# sheet_2_AnalogHeart.net
KiCad netlist of a schematic drawn in Altium Designer
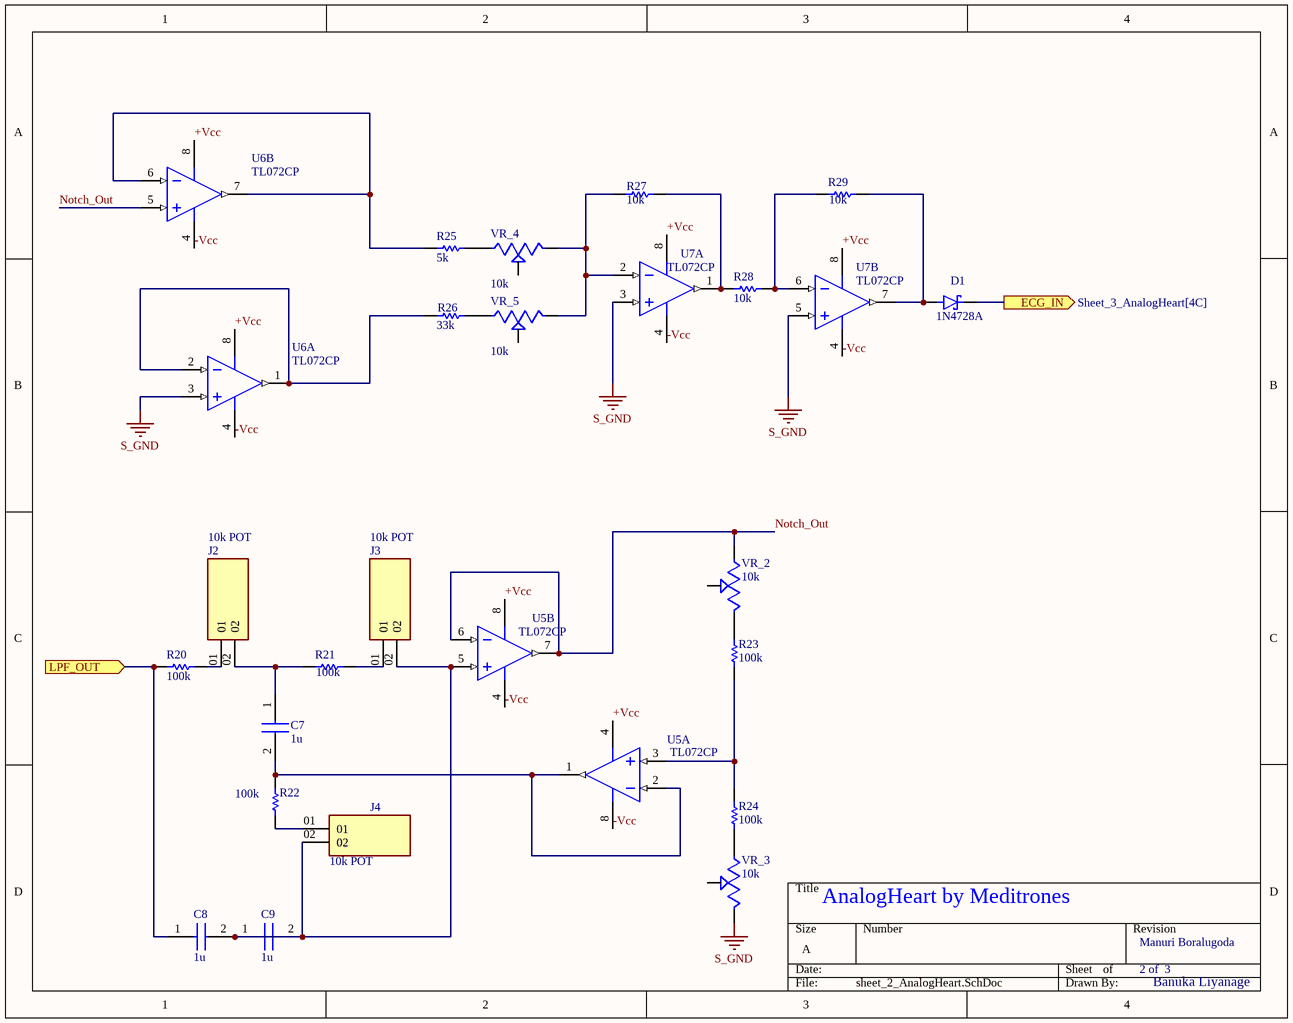
[diagram p0: sheet_2_AnalogHeart.SchDoc]

(export (version "E")
  (design (tool "Eeschema 10.0.6"))
  (components
    (comp (ref "C7")
      (value "1u")
      (footprint "SamacSys:CAPC2012X94N")
      (description "Capacitor")
      (fields
        (field (name "MANUFACTURER_PART_NUMBER") "08055A331FAT2A")
        (field (name "MOUSER PART NUMBER") "581-08055A331FAT2A")
      )
      (libsource (lib "*") (part "08055A331FAT2A"))
    )
    (comp (ref "C8")
      (value "1u")
      (footprint "SamacSys:CAPC2012X94N")
      (description "Capacitor")
      (fields
        (field (name "MANUFACTURER_PART_NUMBER") "08055A331FAT2A")
        (field (name "MOUSER PART NUMBER") "581-08055A331FAT2A")
      )
      (libsource (lib "*") (part "08055A331FAT2A"))
    )
    (comp (ref "C9")
      (value "1u")
      (footprint "SamacSys:CAPC2012X94N")
      (description "Capacitor")
      (fields
        (field (name "MANUFACTURER_PART_NUMBER") "08055A331FAT2A")
        (field (name "MOUSER PART NUMBER") "581-08055A331FAT2A")
      )
      (libsource (lib "*") (part "08055A331FAT2A"))
    )
    (comp (ref "D1")
      (value "1N4728A")
      (footprint "DIOAD1036W78L463D272")
      (description "Ð¡Ñ‚Ð°Ð±Ð¸Ð»Ð¸Ñ‚Ñ€Ð¾Ð½ 3,3 Ð’ 1 Ð’Ñ‚ Â± 5% ÑÐ¾ ÑÐºÐ²Ð¾Ð·Ð½Ñ‹Ð¼ Ð¾Ñ‚Ð²ÐµÑ€ÑÑ‚Ð¸ÐµÐ¼ DO-41")
      (fields (field (name "MF") "ON Semiconductor"))
      (libsource (lib "1N4728A") (part "1N4728A"))
    )
    (comp (ref "J2")
      (value "10k POT")
      (footprint "SAMTEC_MTSW-102-11-T-S-640")
      (fields (field (name "MP") "MTSW-102-11-T-S-640"))
      (libsource (lib "MTSW-102-11-T-S-640") (part "MTSW-102-11-T-S-640"))
    )
    (comp (ref "J3")
      (value "10k POT")
      (footprint "SAMTEC_MTSW-102-11-T-S-640")
      (fields (field (name "MP") "MTSW-102-11-T-S-640"))
      (libsource (lib "MTSW-102-11-T-S-640") (part "MTSW-102-11-T-S-640"))
    )
    (comp (ref "J4")
      (value "10k POT")
      (footprint "SAMTEC_MTSW-102-11-T-S-640")
      (fields (field (name "MP") "MTSW-102-11-T-S-640"))
      (libsource (lib "") (part "MTSW-102-11-T-S-640_1"))
    )
    (comp (ref "R20")
      (value "100k")
      (footprint "RESC2013X50X30NL20T20")
      (fields (field (name "MANUFACTURER") "Vishay Dale") (field (name "PART NUMBER") "CRCW080510R0FKEA"))
      (libsource (lib "Altium Content Vault") (part "RES"))
    )
    (comp (ref "R21")
      (value "100k")
      (footprint "RESC2013X50X30NL20T20")
      (fields (field (name "MANUFACTURER") "Vishay Dale") (field (name "PART NUMBER") "CRCW080510R0FKEA"))
      (libsource (lib "Altium Content Vault") (part "RES"))
    )
    (comp (ref "R22")
      (value "100k")
      (footprint "RESC2013X50X30NL20T20")
      (fields (field (name "MANUFACTURER") "Vishay Dale") (field (name "PART NUMBER") "CRCW080510R0FKEA"))
      (libsource (lib "Altium Content Vault") (part "RES"))
    )
    (comp (ref "R23")
      (value "100k")
      (footprint "RESC2013X50X30NL20T20")
      (fields (field (name "MANUFACTURER") "Vishay Dale") (field (name "PART NUMBER") "CRCW080510R0FKEA"))
      (libsource (lib "Altium Content Vault") (part "RES"))
    )
    (comp (ref "R24")
      (value "100k")
      (footprint "RESC2013X50X30NL20T20")
      (fields (field (name "MANUFACTURER") "Vishay Dale") (field (name "PART NUMBER") "CRCW080510R0FKEA"))
      (libsource (lib "Altium Content Vault") (part "RES"))
    )
    (comp (ref "R25")
      (value "5k")
      (footprint "RESC2013X50X30NL20T20")
      (fields (field (name "MANUFACTURER") "Vishay Dale") (field (name "PART NUMBER") "CRCW080510R0FKEA"))
      (libsource (lib "Altium Content Vault") (part "RES"))
    )
    (comp (ref "R26")
      (value "33k")
      (footprint "RESC2013X50X30NL20T20")
      (fields (field (name "MANUFACTURER") "Vishay Dale") (field (name "PART NUMBER") "CRCW080510R0FKEA"))
      (libsource (lib "Altium Content Vault") (part "RES"))
    )
    (comp (ref "R27")
      (value "10k")
      (footprint "RESC2013X50X30NL20T20")
      (fields (field (name "MANUFACTURER") "Vishay Dale") (field (name "PART NUMBER") "CRCW080510R0FKEA"))
      (libsource (lib "Altium Content Vault") (part "RES"))
    )
    (comp (ref "R28")
      (value "10k")
      (footprint "RESC2013X50X30NL20T20")
      (fields (field (name "MANUFACTURER") "Vishay Dale") (field (name "PART NUMBER") "CRCW080510R0FKEA"))
      (libsource (lib "Altium Content Vault") (part "RES"))
    )
    (comp (ref "R29")
      (value "10k")
      (footprint "RESC2013X50X30NL20T20")
      (fields (field (name "MANUFACTURER") "Vishay Dale") (field (name "PART NUMBER") "CRCW080510R0FKEA"))
      (libsource (lib "Altium Content Vault") (part "RES"))
    )
    (comp (ref "U5")
      (value "TL072CP")
      (footprint "P0008A")
      (fields (field (name "MANUFACTURER") "Texas Instruments"))
      (libsource (lib "Altium Content Vault") (part "TI-AMP-D6-2-8_D"))
    )
    (comp (ref "U6")
      (value "TL072CP")
      (footprint "P0008A")
      (fields (field (name "MANUFACTURER") "Texas Instruments"))
      (libsource (lib "Altium Content Vault") (part "TI-AMP-D6-2-8_D"))
    )
    (comp (ref "U7")
      (value "TL072CP")
      (footprint "P0008A")
      (fields (field (name "MANUFACTURER") "Texas Instruments"))
      (libsource (lib "Altium Content Vault") (part "TI-AMP-D6-2-8_D"))
    )
    (comp (ref "VR_2")
      (value "10k")
      (footprint "TRIM_3386F-1-103TLF")
      (fields (field (name "MF") "Bourns") (field (name "MP") "3386F-1-103TLF"))
      (libsource (lib "3386F-1-103TLF") (part "3386F-1-103TLF"))
    )
    (comp (ref "VR_3")
      (value "10k")
      (footprint "TRIM_3386F-1-103TLF")
      (fields (field (name "MF") "Bourns") (field (name "MP") "3386F-1-103TLF"))
      (libsource (lib "3386F-1-103TLF") (part "3386F-1-103TLF"))
    )
    (comp (ref "VR_4")
      (value "10k")
      (footprint "TRIM_3386F-1-103TLF")
      (fields (field (name "MF") "Bourns") (field (name "MP") "3386F-1-103TLF"))
      (libsource (lib "3386F-1-103TLF") (part "3386F-1-103TLF"))
    )
    (comp (ref "VR_5")
      (value "10k")
      (footprint "TRIM_3386F-1-103TLF")
      (fields (field (name "MF") "Bourns") (field (name "MP") "3386F-1-103TLF"))
      (libsource (lib "3386F-1-103TLF") (part "3386F-1-103TLF"))
    )
  )
  (nets
    (net (code "1") (name "/+Vcc") (class "Default")
      (node (ref "U5") (pin "4") (pinfunction "VCC-_4") (pintype "power_in"))
      (node (ref "U5") (pin "8") (pinfunction "VCC+_8") (pintype "power_in"))
      (node (ref "U6") (pin "8") (pinfunction "VCC+_8") (pintype "power_in"))
      (node (ref "U7") (pin "8") (pinfunction "VCC+_8") (pintype "power_in"))
    )
    (net (code "2") (name "/-Vcc") (class "Default")
      (node (ref "U5") (pin "4") (pinfunction "VCC-_4") (pintype "power_in"))
      (node (ref "U5") (pin "8") (pinfunction "VCC+_8") (pintype "power_in"))
      (node (ref "U6") (pin "4") (pinfunction "VCC-_4") (pintype "power_in"))
      (node (ref "U7") (pin "4") (pinfunction "VCC-_4") (pintype "power_in"))
    )
    (net (code "3") (name "/ECG_IN") (class "Default")
      (node (ref "D1") (pin "1") (pinfunction "K_1") (pintype "passive"))
    )
    (net (code "4") (name "/LPF_OUT") (class "Default")
      (node (ref "C8") (pin "1") (pinfunction "1_1") (pintype "passive"))
      (node (ref "R20") (pin "2") (pinfunction "2_2") (pintype "passive"))
    )
    (net (code "5") (name "/Notch_Out") (class "Default")
      (node (ref "U5") (pin "6") (pinfunction "IN2-_6") (pintype "input"))
      (node (ref "U5") (pin "7") (pinfunction "OUT2_7") (pintype "output"))
      (node (ref "U6") (pin "5") (pinfunction "IN2+_5") (pintype "input"))
      (node (ref "VR_2") (pin "1") (pinfunction "CCW_1") (pintype "passive"))
    )
    (net (code "6") (name "Net-(C7-Pad1)") (class "Default")
      (node (ref "C7") (pin "1") (pinfunction "1_1") (pintype "passive"))
      (node (ref "J2") (pin "02") (pinfunction "02_02") (pintype "passive"))
      (node (ref "R21") (pin "2") (pinfunction "2_2") (pintype "passive"))
    )
    (net (code "7") (name "Net-(D1-A)") (class "Default")
      (node (ref "D1") (pin "2") (pinfunction "A_2") (pintype "passive"))
      (node (ref "R29") (pin "1") (pinfunction "1_1") (pintype "passive"))
      (node (ref "U7") (pin "7") (pinfunction "OUT2_7") (pintype "output"))
    )
    (net (code "8") (name "Net-(J2-Pad01)") (class "Default")
      (node (ref "J2") (pin "01") (pinfunction "01_01") (pintype "passive"))
      (node (ref "R20") (pin "1") (pinfunction "1_1") (pintype "passive"))
    )
    (net (code "9") (name "Net-(J3-Pad01)") (class "Default")
      (node (ref "J3") (pin "01") (pinfunction "01_01") (pintype "passive"))
      (node (ref "R21") (pin "1") (pinfunction "1_1") (pintype "passive"))
    )
    (net (code "10") (name "Net-(J4-Pad01)") (class "Default")
      (node (ref "J4") (pin "01") (pinfunction "01_01") (pintype "passive"))
      (node (ref "R22") (pin "2") (pinfunction "2_2") (pintype "passive"))
    )
    (net (code "11") (name "Net-(U5A-IN1+)") (class "Default")
      (node (ref "R23") (pin "2") (pinfunction "2_2") (pintype "passive"))
      (node (ref "R24") (pin "1") (pinfunction "1_1") (pintype "passive"))
      (node (ref "U5") (pin "3") (pinfunction "IN1+_3") (pintype "input"))
    )
    (net (code "12") (name "Net-(U5A-IN1-)") (class "Default")
      (node (ref "C7") (pin "2") (pinfunction "2_2") (pintype "passive"))
      (node (ref "R22") (pin "1") (pinfunction "1_1") (pintype "passive"))
      (node (ref "U5") (pin "1") (pinfunction "OUT1_1") (pintype "output"))
      (node (ref "U5") (pin "2") (pinfunction "IN1-_2") (pintype "input"))
    )
    (net (code "13") (name "Net-(U5B-IN2+)") (class "Default")
      (node (ref "C8") (pin "2") (pinfunction "2_2") (pintype "passive"))
      (node (ref "C9") (pin "1") (pinfunction "1_1") (pintype "passive"))
      (node (ref "C9") (pin "2") (pinfunction "2_2") (pintype "passive"))
      (node (ref "J3") (pin "02") (pinfunction "02_02") (pintype "passive"))
      (node (ref "J4") (pin "02") (pinfunction "02_02") (pintype "passive"))
      (node (ref "U5") (pin "5") (pinfunction "IN2+_5") (pintype "input"))
    )
    (net (code "14") (name "Net-(U6A-IN1-)") (class "Default")
      (node (ref "R26") (pin "2") (pinfunction "2_2") (pintype "passive"))
      (node (ref "U6") (pin "1") (pinfunction "OUT1_1") (pintype "output"))
      (node (ref "U6") (pin "2") (pinfunction "IN1-_2") (pintype "input"))
    )
    (net (code "15") (name "Net-(U6B-IN2-)") (class "Default")
      (node (ref "R25") (pin "2") (pinfunction "2_2") (pintype "passive"))
      (node (ref "U6") (pin "6") (pinfunction "IN2-_6") (pintype "input"))
      (node (ref "U6") (pin "7") (pinfunction "OUT2_7") (pintype "output"))
    )
    (net (code "16") (name "Net-(U7A-IN1-)") (class "Default")
      (node (ref "R27") (pin "2") (pinfunction "2_2") (pintype "passive"))
      (node (ref "U7") (pin "2") (pinfunction "IN1-_2") (pintype "input"))
      (node (ref "VR_4") (pin "3") (pinfunction "CW_3") (pintype "passive"))
      (node (ref "VR_5") (pin "3") (pinfunction "CW_3") (pintype "passive"))
    )
    (net (code "17") (name "Net-(U7A-OUT1)") (class "Default")
      (node (ref "R27") (pin "1") (pinfunction "1_1") (pintype "passive"))
      (node (ref "R28") (pin "2") (pinfunction "2_2") (pintype "passive"))
      (node (ref "U7") (pin "1") (pinfunction "OUT1_1") (pintype "output"))
    )
    (net (code "18") (name "Net-(U7B-IN2-)") (class "Default")
      (node (ref "R28") (pin "1") (pinfunction "1_1") (pintype "passive"))
      (node (ref "R29") (pin "2") (pinfunction "2_2") (pintype "passive"))
      (node (ref "U7") (pin "6") (pinfunction "IN2-_6") (pintype "input"))
    )
    (net (code "19") (name "Net-(VR_2-CW)") (class "Default")
      (node (ref "R23") (pin "1") (pinfunction "1_1") (pintype "passive"))
      (node (ref "VR_2") (pin "3") (pinfunction "CW_3") (pintype "passive"))
    )
    (net (code "20") (name "Net-(VR_3-CCW)") (class "Default")
      (node (ref "R24") (pin "2") (pinfunction "2_2") (pintype "passive"))
      (node (ref "VR_3") (pin "1") (pinfunction "CCW_1") (pintype "passive"))
    )
    (net (code "21") (name "Net-(VR_4-CCW)") (class "Default")
      (node (ref "R25") (pin "1") (pinfunction "1_1") (pintype "passive"))
      (node (ref "VR_4") (pin "1") (pinfunction "CCW_1") (pintype "passive"))
    )
    (net (code "22") (name "Net-(VR_5-CCW)") (class "Default")
      (node (ref "R26") (pin "1") (pinfunction "1_1") (pintype "passive"))
      (node (ref "VR_5") (pin "1") (pinfunction "CCW_1") (pintype "passive"))
    )
    (net (code "23") (name "S_GND") (class "Default")
      (node (ref "U6") (pin "3") (pinfunction "IN1+_3") (pintype "input"))
      (node (ref "U7") (pin "3") (pinfunction "IN1+_3") (pintype "input"))
      (node (ref "U7") (pin "5") (pinfunction "IN2+_5") (pintype "input"))
      (node (ref "VR_3") (pin "3") (pinfunction "CW_3") (pintype "passive"))
    )
    (net (code "24") (name "unconnected-(VR_2-WIPER-Pad2)") (class "Default")
      (node (ref "VR_2") (pin "2") (pinfunction "WIPER_2") (pintype "passive"))
    )
    (net (code "25") (name "unconnected-(VR_3-WIPER-Pad2)") (class "Default")
      (node (ref "VR_3") (pin "2") (pinfunction "WIPER_2") (pintype "passive"))
    )
    (net (code "26") (name "unconnected-(VR_4-WIPER-Pad2)") (class "Default")
      (node (ref "VR_4") (pin "2") (pinfunction "WIPER_2") (pintype "passive"))
    )
    (net (code "27") (name "unconnected-(VR_5-WIPER-Pad2)") (class "Default")
      (node (ref "VR_5") (pin "2") (pinfunction "WIPER_2") (pintype "passive"))
    )
  )
)
